# TimeTracker_TestboardV1.net
KiCad netlist of a schematic drawn in EAGLE
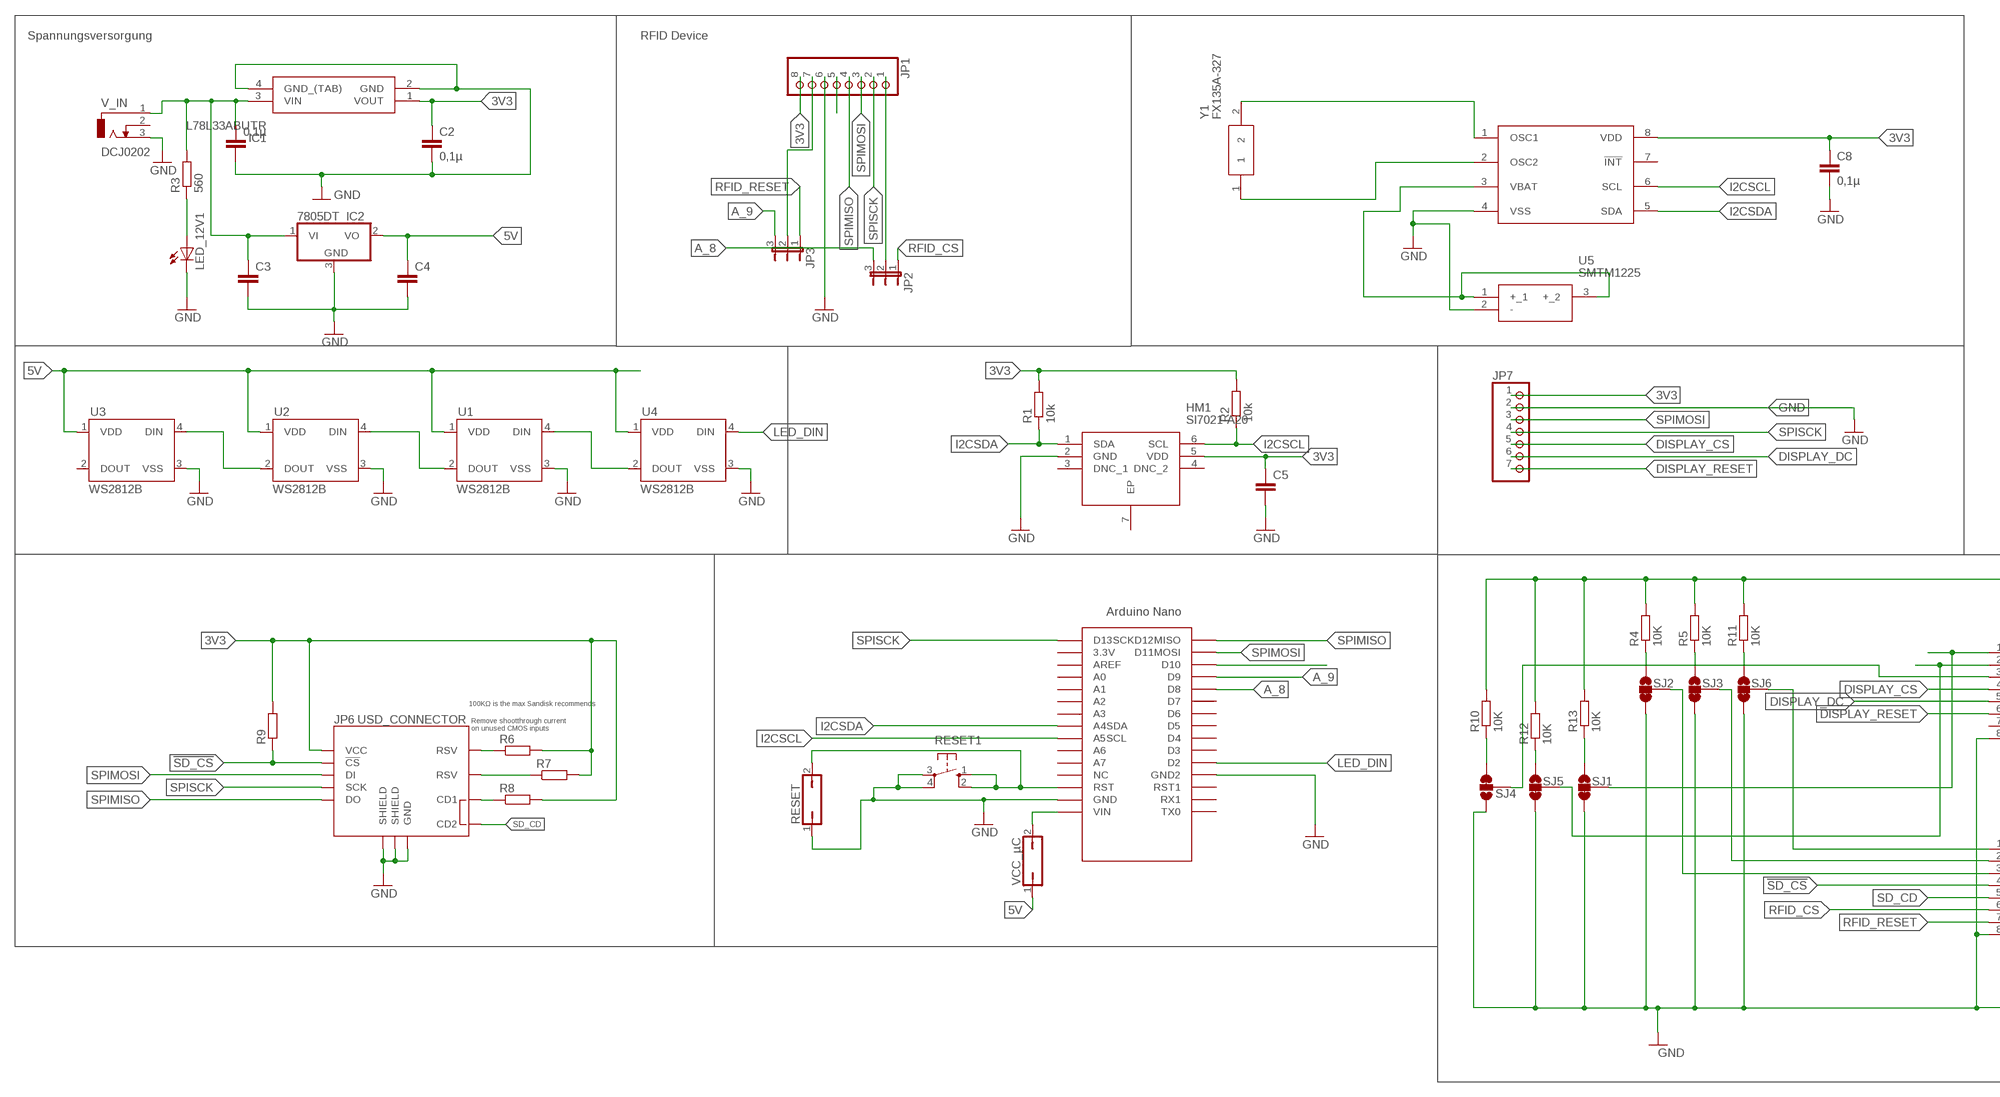
[diagram p0: schematic, sheet 1, part 1 of 2]
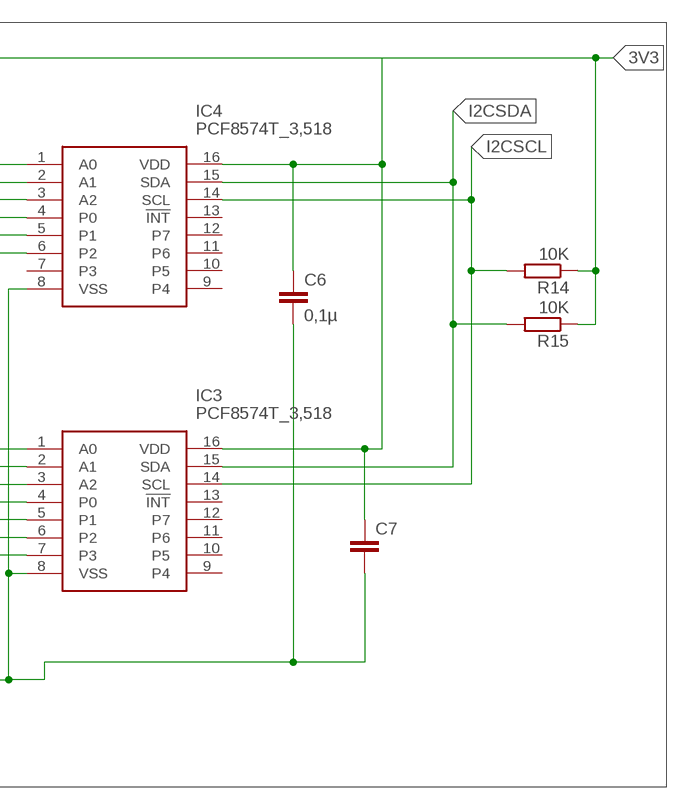
[diagram p1: schematic, sheet 1, part 2 of 2]

(export (version "E")
  (design (tool "Eeschema 10.0.6"))
  (components
    (comp (ref "0.1µ")
      (value "C-EUC0805")
      (footprint "eagle-import:C0805")
      (libsource (lib "eagle-import") (part "C-EUC0805"))
    )
    (comp (ref "C2")
      (value "0,1µ")
      (footprint "eagle-import:C0805")
      (libsource (lib "eagle-import") (part "C-EUC0805"))
    )
    (comp (ref "C3")
      (value "C-EUC0805")
      (footprint "eagle-import:C0805")
      (libsource (lib "eagle-import") (part "C-EUC0805"))
    )
    (comp (ref "C4")
      (value "C-EUC0805")
      (footprint "eagle-import:C0805")
      (libsource (lib "eagle-import") (part "C-EUC0805"))
    )
    (comp (ref "C5")
      (value "C-EUC0805")
      (footprint "eagle-import:C0805")
      (libsource (lib "eagle-import") (part "C-EUC0805"))
    )
    (comp (ref "C6")
      (value "0,1µ")
      (footprint "eagle-import:C0805")
      (libsource (lib "eagle-import") (part "C-EUC0805"))
    )
    (comp (ref "C7")
      (value "C-EUC0805")
      (footprint "eagle-import:C0805")
      (libsource (lib "eagle-import") (part "C-EUC0805"))
    )
    (comp (ref "C8")
      (value "0,1µ")
      (footprint "eagle-import:C0805")
      (libsource (lib "eagle-import") (part "C-EUC0805"))
    )
    (comp (ref "HM1")
      (value "SI7021-A20")
      (footprint "eagle-import:SON100P300X300X80-7N")
      (fields (field (name "MANUFACTURER_PART_NUMBER") "Si7021-A20"))
      (libsource (lib "eagle-import") (part "SI7021-A20"))
    )
    (comp (ref "IC1")
      (value "L78L33ABUTR")
      (footprint "eagle-import:ST-SOT-89")
      (fields
        (field (name "MOUSER_PART_NUMBER") "511-L78L33ABU-TR")
        (field (name "RS_PART_NUMBER") "6869464P")
      )
      (libsource (lib "eagle-import") (part "L78L33ABUTR"))
    )
    (comp (ref "IC2")
      (value "7805DT")
      (footprint "eagle-import:TO252")
      (libsource (lib "eagle-import") (part "78DT05"))
    )
    (comp (ref "IC3")
      (value "PCF8574T_3,518")
      (footprint "eagle-import:SOIC127P1032X265-16N")
      (fields
        (field (name "MANUFACTURER_PART_NUMBER") "PCF8574T/3,518")
        (field (name "MOUSER_PART_NUMBER") "771-PCF8574TD-T")
      )
      (libsource (lib "eagle-import") (part "PCF8574T_3,518"))
    )
    (comp (ref "IC4")
      (value "PCF8574T_3,518")
      (footprint "eagle-import:SOIC127P1032X265-16N")
      (fields
        (field (name "MANUFACTURER_PART_NUMBER") "PCF8574T/3,518")
        (field (name "MOUSER_PART_NUMBER") "771-PCF8574TD-T")
      )
      (libsource (lib "eagle-import") (part "PCF8574T_3,518"))
    )
    (comp (ref "JP1")
      (value "PINHD-1X8")
      (footprint "eagle-import:1X08")
      (libsource (lib "eagle-import") (part "PINHD-1X8"))
    )
    (comp (ref "JP2")
      (value "JP2E")
      (footprint "eagle-import:JP2")
      (libsource (lib "eagle-import") (part "JP2E"))
    )
    (comp (ref "JP3")
      (value "JP2E")
      (footprint "eagle-import:JP2")
      (libsource (lib "eagle-import") (part "JP2E"))
    )
    (comp (ref "JP6")
      (value "USD_CONNECTOR")
      (footprint "eagle-import:MICRO-SD-SOCKET-PP")
      (libsource (lib "eagle-import") (part "USD_CONNECTOR"))
    )
    (comp (ref "JP7")
      (value "PINHD-1X7")
      (footprint "eagle-import:1X07")
      (libsource (lib "eagle-import") (part "PINHD-1X7"))
    )
    (comp (ref "LED_12V1")
      (value "LEDSML0805")
      (footprint "eagle-import:SML0805")
      (libsource (lib "eagle-import") (part "LEDSML0805"))
    )
    (comp (ref "R1")
      (value "10k")
      (footprint "eagle-import:R0805")
      (libsource (lib "eagle-import") (part "R-EU_R0805"))
    )
    (comp (ref "R2")
      (value "10k")
      (footprint "eagle-import:R0805")
      (libsource (lib "eagle-import") (part "R-EU_R0805"))
    )
    (comp (ref "R3")
      (value "560")
      (footprint "eagle-import:R0805")
      (libsource (lib "eagle-import") (part "R-EU_R0805"))
    )
    (comp (ref "R4")
      (value "10K")
      (footprint "eagle-import:R0805")
      (libsource (lib "eagle-import") (part "R-EU_R0805"))
    )
    (comp (ref "R5")
      (value "10K")
      (footprint "eagle-import:R0805")
      (libsource (lib "eagle-import") (part "R-EU_R0805"))
    )
    (comp (ref "R6")
      (value "100k")
      (footprint "eagle-import:R0805")
      (libsource (lib "eagle-import") (part "R-EU_R0805"))
    )
    (comp (ref "R7")
      (value "100k")
      (footprint "eagle-import:R0805")
      (libsource (lib "eagle-import") (part "R-EU_R0805"))
    )
    (comp (ref "R8")
      (value "100k")
      (footprint "eagle-import:R0805")
      (libsource (lib "eagle-import") (part "R-EU_R0805"))
    )
    (comp (ref "R9")
      (value "100k")
      (footprint "eagle-import:R0805")
      (libsource (lib "eagle-import") (part "R-EU_R0805"))
    )
    (comp (ref "R10")
      (value "10K")
      (footprint "eagle-import:R0805")
      (libsource (lib "eagle-import") (part "R-EU_R0805"))
    )
    (comp (ref "R11")
      (value "10K")
      (footprint "eagle-import:R0805")
      (libsource (lib "eagle-import") (part "R-EU_R0805"))
    )
    (comp (ref "R12")
      (value "10K")
      (footprint "eagle-import:R0805")
      (libsource (lib "eagle-import") (part "R-EU_R0805"))
    )
    (comp (ref "R13")
      (value "10K")
      (footprint "eagle-import:R0805")
      (libsource (lib "eagle-import") (part "R-EU_R0805"))
    )
    (comp (ref "R14")
      (value "10K")
      (footprint "eagle-import:R0805")
      (libsource (lib "eagle-import") (part "R-EU_R0805"))
    )
    (comp (ref "R15")
      (value "10K")
      (footprint "eagle-import:R0805")
      (libsource (lib "eagle-import") (part "R-EU_R0805"))
    )
    (comp (ref "RESET")
      (value "JP1Q")
      (footprint "eagle-import:JP1")
      (libsource (lib "eagle-import") (part "JP1Q"))
    )
    (comp (ref "RESET1")
      (value "10-XX")
      (footprint "eagle-import:B3F-10XX")
      (fields (field (name "MPN") "B3F-1000"))
      (libsource (lib "eagle-import") (part "10-XX"))
    )
    (comp (ref "SJ1")
      (value "JUMPER-PAD-3-2OF3_NC_BY_TRACE_SMALL")
      (footprint "eagle-import:PAD-JUMPER-3-2OF3_NC_BY_TRACE_YES_SILK_FULL_BOX")
      (libsource (lib "eagle-import") (part "JUMPER-PAD-3-2OF3_NC_BY_TRACE_SMALL"))
    )
    (comp (ref "SJ2")
      (value "JUMPER-PAD-3-2OF3_NC_BY_TRACE_SMALL")
      (footprint "eagle-import:PAD-JUMPER-3-2OF3_NC_BY_TRACE_YES_SILK_FULL_BOX")
      (libsource (lib "eagle-import") (part "JUMPER-PAD-3-2OF3_NC_BY_TRACE_SMALL"))
    )
    (comp (ref "SJ3")
      (value "JUMPER-PAD-3-2OF3_NC_BY_TRACE_SMALL")
      (footprint "eagle-import:PAD-JUMPER-3-2OF3_NC_BY_TRACE_YES_SILK_FULL_BOX")
      (libsource (lib "eagle-import") (part "JUMPER-PAD-3-2OF3_NC_BY_TRACE_SMALL"))
    )
    (comp (ref "SJ4")
      (value "JUMPER-PAD-3-2OF3_NC_BY_TRACE_SMALL")
      (footprint "eagle-import:PAD-JUMPER-3-2OF3_NC_BY_TRACE_YES_SILK_FULL_BOX")
      (libsource (lib "eagle-import") (part "JUMPER-PAD-3-2OF3_NC_BY_TRACE_SMALL"))
    )
    (comp (ref "SJ5")
      (value "JUMPER-PAD-3-2OF3_NC_BY_TRACE_SMALL")
      (footprint "eagle-import:PAD-JUMPER-3-2OF3_NC_BY_TRACE_YES_SILK_FULL_BOX")
      (libsource (lib "eagle-import") (part "JUMPER-PAD-3-2OF3_NC_BY_TRACE_SMALL"))
    )
    (comp (ref "SJ6")
      (value "JUMPER-PAD-3-2OF3_NC_BY_TRACE_SMALL")
      (footprint "eagle-import:PAD-JUMPER-3-2OF3_NC_BY_TRACE_YES_SILK_FULL_BOX")
      (libsource (lib "eagle-import") (part "JUMPER-PAD-3-2OF3_NC_BY_TRACE_SMALL"))
    )
    (comp (ref "U$1")
      (value "NANO")
      (footprint "eagle-import:NANO")
      (libsource (lib "eagle-import") (part "NANO"))
    )
    (comp (ref "U$2")
      (value "RTC")
      (footprint "eagle-import:SOP65P490X110-8N")
      (libsource (lib "eagle-import") (part "RTC"))
    )
    (comp (ref "U1")
      (value "WS2812B")
      (footprint "eagle-import:WS2812B")
      (libsource (lib "eagle-import") (part "WS2812B"))
    )
    (comp (ref "U2")
      (value "WS2812B")
      (footprint "eagle-import:WS2812B")
      (libsource (lib "eagle-import") (part "WS2812B"))
    )
    (comp (ref "U3")
      (value "WS2812B")
      (footprint "eagle-import:WS2812B")
      (libsource (lib "eagle-import") (part "WS2812B"))
    )
    (comp (ref "U4")
      (value "WS2812B")
      (footprint "eagle-import:WS2812B")
      (libsource (lib "eagle-import") (part "WS2812B"))
    )
    (comp (ref "U5")
      (value "SMTM1225")
      (footprint "eagle-import:SMTM1225")
      (fields (field (name "MOUSER_PART_NUMBER") "614-SMTM1225"))
      (libsource (lib "eagle-import") (part "SMTM1225"))
    )
    (comp (ref "VCC_µC")
      (value "JP1Q")
      (footprint "eagle-import:JP1")
      (libsource (lib "eagle-import") (part "JP1Q"))
    )
    (comp (ref "V_IN")
      (value "DCJ0202")
      (footprint "eagle-import:DCJ0202")
      (libsource (lib "eagle-import") (part "DCJ0202"))
    )
    (comp (ref "Y1")
      (value "FX135A-327")
      (footprint "eagle-import:FX135")
      (fields (field (name "MOUSER_PART_NUMBER") "559-FX135A-327") (field (name "RS_PART_NUMBER") "6480200P"))
      (libsource (lib "eagle-import") (part "FX135A-327"))
    )
  )
  (nets
    (net (code "1") (name "/EP") (class "Default")
      (node (ref "HM1") (pin "7") (pinfunction "EP_7") (pintype "power_in"))
    )
    (net (code "2") (name "/~{SD_CS}") (class "Default")
      (node (ref "IC3") (pin "4") (pinfunction "P0_4") (pintype "bidirectional"))
      (node (ref "JP6") (pin "CS") (pinfunction "~{CS}_CS") (pintype "bidirectional"))
      (node (ref "R9") (pin "1") (pinfunction "1_1") (pintype "passive"))
    )
    (net (code "3") (name "3V3") (class "Default")
      (node (ref "C2") (pin "1") (pinfunction "1_1") (pintype "passive"))
      (node (ref "C5") (pin "1") (pinfunction "1_1") (pintype "passive"))
      (node (ref "C6") (pin "1") (pinfunction "1_1") (pintype "passive"))
      (node (ref "C7") (pin "1") (pinfunction "1_1") (pintype "passive"))
      (node (ref "C8") (pin "1") (pinfunction "1_1") (pintype "passive"))
      (node (ref "HM1") (pin "5") (pinfunction "VDD_5") (pintype "power_in"))
      (node (ref "IC1") (pin "1") (pinfunction "VOUT_1") (pintype "output"))
      (node (ref "IC3") (pin "16") (pinfunction "VDD_16") (pintype "bidirectional"))
      (node (ref "IC4") (pin "16") (pinfunction "VDD_16") (pintype "bidirectional"))
      (node (ref "JP1") (pin "8") (pinfunction "8_8") (pintype "passive"))
      (node (ref "JP6") (pin "VCC") (pinfunction "VCC_VCC") (pintype "bidirectional"))
      (node (ref "JP7") (pin "1") (pinfunction "1_1") (pintype "passive"))
      (node (ref "R1") (pin "2") (pinfunction "2_2") (pintype "passive"))
      (node (ref "R10") (pin "2") (pinfunction "2_2") (pintype "passive"))
      (node (ref "R11") (pin "2") (pinfunction "2_2") (pintype "passive"))
      (node (ref "R12") (pin "2") (pinfunction "2_2") (pintype "passive"))
      (node (ref "R13") (pin "2") (pinfunction "2_2") (pintype "passive"))
      (node (ref "R14") (pin "1") (pinfunction "1_1") (pintype "passive"))
      (node (ref "R15") (pin "1") (pinfunction "1_1") (pintype "passive"))
      (node (ref "R2") (pin "2") (pinfunction "2_2") (pintype "passive"))
      (node (ref "R4") (pin "2") (pinfunction "2_2") (pintype "passive"))
      (node (ref "R5") (pin "2") (pinfunction "2_2") (pintype "passive"))
      (node (ref "R6") (pin "2") (pinfunction "2_2") (pintype "passive"))
      (node (ref "R7") (pin "2") (pinfunction "2_2") (pintype "passive"))
      (node (ref "R8") (pin "2") (pinfunction "2_2") (pintype "passive"))
      (node (ref "R9") (pin "2") (pinfunction "2_2") (pintype "passive"))
      (node (ref "U$2") (pin "8") (pinfunction "VDD_8") (pintype "bidirectional"))
    )
    (net (code "4") (name "5V") (class "Default")
      (node (ref "C4") (pin "1") (pinfunction "1_1") (pintype "passive"))
      (node (ref "IC2") (pin "2") (pinfunction "VO_2") (pintype "passive"))
      (node (ref "U1") (pin "1") (pinfunction "VDD_1") (pintype "power_in"))
      (node (ref "U2") (pin "1") (pinfunction "VDD_1") (pintype "power_in"))
      (node (ref "U3") (pin "1") (pinfunction "VDD_1") (pintype "power_in"))
      (node (ref "U4") (pin "1") (pinfunction "VDD_1") (pintype "power_in"))
      (node (ref "VCC_µC") (pin "1") (pinfunction "1_1") (pintype "passive"))
    )
    (net (code "5") (name "A_8") (class "Default")
      (node (ref "JP2") (pin "3") (pinfunction "3_3") (pintype "passive"))
      (node (ref "U$1") (pin "D8") (pinfunction "D8_D8") (pintype "bidirectional"))
    )
    (net (code "6") (name "A_9") (class "Default")
      (node (ref "JP3") (pin "3") (pinfunction "3_3") (pintype "passive"))
      (node (ref "U$1") (pin "D9") (pinfunction "D9_D9") (pintype "bidirectional"))
    )
    (net (code "7") (name "DISPLAY_CS") (class "Default")
      (node (ref "IC4") (pin "4") (pinfunction "P0_4") (pintype "bidirectional"))
      (node (ref "JP7") (pin "5") (pinfunction "5_5") (pintype "passive"))
    )
    (net (code "8") (name "DISPLAY_DC") (class "Default")
      (node (ref "IC4") (pin "5") (pinfunction "P1_5") (pintype "bidirectional"))
      (node (ref "JP7") (pin "6") (pinfunction "6_6") (pintype "passive"))
    )
    (net (code "9") (name "DISPLAY_RESET") (class "Default")
      (node (ref "IC4") (pin "6") (pinfunction "P2_6") (pintype "bidirectional"))
      (node (ref "JP7") (pin "7") (pinfunction "7_7") (pintype "passive"))
    )
    (net (code "10") (name "GND") (class "Default")
      (node (ref "0.1µ") (pin "2") (pinfunction "2_2") (pintype "passive"))
      (node (ref "C2") (pin "2") (pinfunction "2_2") (pintype "passive"))
      (node (ref "C3") (pin "2") (pinfunction "2_2") (pintype "passive"))
      (node (ref "C4") (pin "2") (pinfunction "2_2") (pintype "passive"))
      (node (ref "C5") (pin "2") (pinfunction "2_2") (pintype "passive"))
      (node (ref "C6") (pin "2") (pinfunction "2_2") (pintype "passive"))
      (node (ref "C7") (pin "2") (pinfunction "2_2") (pintype "passive"))
      (node (ref "C8") (pin "2") (pinfunction "2_2") (pintype "passive"))
      (node (ref "HM1") (pin "2") (pinfunction "GND_2") (pintype "power_in"))
      (node (ref "IC1") (pin "2") (pinfunction "GND_2") (pintype "power_in"))
      (node (ref "IC1") (pin "4") (pinfunction "GND_(TAB)_4") (pintype "power_in"))
      (node (ref "IC2") (pin "3") (pinfunction "GND_3") (pintype "passive"))
      (node (ref "IC3") (pin "8") (pinfunction "VSS_8") (pintype "bidirectional"))
      (node (ref "IC4") (pin "8") (pinfunction "VSS_8") (pintype "bidirectional"))
      (node (ref "JP1") (pin "6") (pinfunction "6_6") (pintype "passive"))
      (node (ref "JP6") (pin "GND") (pinfunction "GND_GND") (pintype "bidirectional"))
      (node (ref "JP6") (pin "GND1") (pinfunction "SHIELD_GND1") (pintype "bidirectional"))
      (node (ref "JP6") (pin "GND3") (pinfunction "SHIELD_GND3") (pintype "bidirectional"))
      (node (ref "JP7") (pin "2") (pinfunction "2_2") (pintype "passive"))
      (node (ref "LED_12V1") (pin "C") (pinfunction "C_C") (pintype "passive"))
      (node (ref "RESET") (pin "1") (pinfunction "1_1") (pintype "passive"))
      (node (ref "RESET1") (pin "3") (pinfunction "P_3") (pintype "passive"))
      (node (ref "RESET1") (pin "4") (pinfunction "P1_4") (pintype "passive"))
      (node (ref "SJ1") (pin "3") (pinfunction "3_3") (pintype "passive"))
      (node (ref "SJ2") (pin "3") (pinfunction "3_3") (pintype "passive"))
      (node (ref "SJ3") (pin "3") (pinfunction "3_3") (pintype "passive"))
      (node (ref "SJ4") (pin "1") (pinfunction "1_1") (pintype "passive"))
      (node (ref "SJ5") (pin "3") (pinfunction "3_3") (pintype "passive"))
      (node (ref "SJ6") (pin "3") (pinfunction "3_3") (pintype "passive"))
      (node (ref "U$1") (pin "GND") (pinfunction "GND_GND") (pintype "bidirectional"))
      (node (ref "U$1") (pin "GND1") (pinfunction "GND2_GND1") (pintype "bidirectional"))
      (node (ref "U$2") (pin "4") (pinfunction "VSS_4") (pintype "bidirectional"))
      (node (ref "U1") (pin "3") (pinfunction "VSS_3") (pintype "power_in"))
      (node (ref "U2") (pin "3") (pinfunction "VSS_3") (pintype "power_in"))
      (node (ref "U3") (pin "3") (pinfunction "VSS_3") (pintype "power_in"))
      (node (ref "U4") (pin "3") (pinfunction "VSS_3") (pintype "power_in"))
      (node (ref "U5") (pin "2") (pinfunction "-_2") (pintype "bidirectional"))
      (node (ref "V_IN") (pin "3") (pinfunction "3_3") (pintype "passive"))
    )
    (net (code "11") (name "I2CSCL") (class "Default")
      (node (ref "HM1") (pin "6") (pinfunction "SCL_6") (pintype "bidirectional"))
      (node (ref "IC3") (pin "14") (pinfunction "SCL_14") (pintype "bidirectional"))
      (node (ref "IC4") (pin "14") (pinfunction "SCL_14") (pintype "bidirectional"))
      (node (ref "R14") (pin "2") (pinfunction "2_2") (pintype "passive"))
      (node (ref "R2") (pin "1") (pinfunction "1_1") (pintype "passive"))
      (node (ref "U$1") (pin "A5") (pinfunction "A5SCL_A5") (pintype "bidirectional"))
      (node (ref "U$2") (pin "6") (pinfunction "SCL_6") (pintype "bidirectional"))
    )
    (net (code "12") (name "I2CSDA") (class "Default")
      (node (ref "HM1") (pin "1") (pinfunction "SDA_1") (pintype "bidirectional"))
      (node (ref "IC3") (pin "15") (pinfunction "SDA_15") (pintype "bidirectional"))
      (node (ref "IC4") (pin "15") (pinfunction "SDA_15") (pintype "bidirectional"))
      (node (ref "R1") (pin "1") (pinfunction "1_1") (pintype "passive"))
      (node (ref "R15") (pin "2") (pinfunction "2_2") (pintype "passive"))
      (node (ref "U$1") (pin "A4") (pinfunction "A4SDA_A4") (pintype "bidirectional"))
      (node (ref "U$2") (pin "5") (pinfunction "SDA_5") (pintype "bidirectional"))
    )
    (net (code "13") (name "LED_DIN") (class "Default")
      (node (ref "U$1") (pin "D2") (pinfunction "D2_D2") (pintype "bidirectional"))
      (node (ref "U4") (pin "4") (pinfunction "DIN_4") (pintype "input"))
    )
    (net (code "14") (name "Net-(IC1-VIN)") (class "Default")
      (node (ref "0.1µ") (pin "1") (pinfunction "1_1") (pintype "passive"))
      (node (ref "C3") (pin "1") (pinfunction "1_1") (pintype "passive"))
      (node (ref "IC1") (pin "3") (pinfunction "VIN_3") (pintype "input"))
      (node (ref "IC2") (pin "1") (pinfunction "VI_1") (pintype "input"))
      (node (ref "R3") (pin "2") (pinfunction "2_2") (pintype "passive"))
      (node (ref "V_IN") (pin "1") (pinfunction "1_1") (pintype "passive"))
    )
    (net (code "15") (name "Net-(IC3-A0)") (class "Default")
      (node (ref "IC3") (pin "1") (pinfunction "A0_1") (pintype "bidirectional"))
      (node (ref "SJ6") (pin "2") (pinfunction "2_2") (pintype "passive"))
    )
    (net (code "16") (name "Net-(IC3-A1)") (class "Default")
      (node (ref "IC3") (pin "2") (pinfunction "A1_2") (pintype "bidirectional"))
      (node (ref "SJ3") (pin "2") (pinfunction "2_2") (pintype "passive"))
    )
    (net (code "17") (name "Net-(IC3-A2)") (class "Default")
      (node (ref "IC3") (pin "3") (pinfunction "A2_3") (pintype "bidirectional"))
      (node (ref "SJ2") (pin "2") (pinfunction "2_2") (pintype "passive"))
    )
    (net (code "18") (name "Net-(IC4-A0)") (class "Default")
      (node (ref "IC4") (pin "1") (pinfunction "A0_1") (pintype "bidirectional"))
      (node (ref "SJ1") (pin "2") (pinfunction "2_2") (pintype "passive"))
    )
    (net (code "19") (name "Net-(IC4-A1)") (class "Default")
      (node (ref "IC4") (pin "2") (pinfunction "A1_2") (pintype "bidirectional"))
      (node (ref "SJ5") (pin "2") (pinfunction "2_2") (pintype "passive"))
    )
    (net (code "20") (name "Net-(IC4-A2)") (class "Default")
      (node (ref "IC4") (pin "3") (pinfunction "A2_3") (pintype "bidirectional"))
      (node (ref "SJ4") (pin "2") (pinfunction "2_2") (pintype "passive"))
    )
    (net (code "21") (name "Net-(JP1-Pad1)") (class "Default")
      (node (ref "JP1") (pin "1") (pinfunction "1_1") (pintype "passive"))
      (node (ref "JP2") (pin "2") (pinfunction "2_2") (pintype "passive"))
    )
    (net (code "22") (name "Net-(JP1-Pad7)") (class "Default")
      (node (ref "JP1") (pin "7") (pinfunction "7_7") (pintype "passive"))
      (node (ref "JP3") (pin "2") (pinfunction "2_2") (pintype "passive"))
    )
    (net (code "23") (name "Net-(JP6-PadCD1)") (class "Default")
      (node (ref "JP6") (pin "CD1") (pinfunction "CD1_CD1") (pintype "bidirectional"))
      (node (ref "R8") (pin "1") (pinfunction "1_1") (pintype "passive"))
    )
    (net (code "24") (name "Net-(JP6-RSV-PadRSV1)") (class "Default")
      (node (ref "JP6") (pin "RSV1") (pinfunction "RSV_RSV1") (pintype "bidirectional"))
      (node (ref "R6") (pin "1") (pinfunction "1_1") (pintype "passive"))
    )
    (net (code "25") (name "Net-(JP6-RSV-PadRSV2)") (class "Default")
      (node (ref "JP6") (pin "RSV2") (pinfunction "RSV_RSV2") (pintype "bidirectional"))
      (node (ref "R7") (pin "1") (pinfunction "1_1") (pintype "passive"))
    )
    (net (code "26") (name "Net-(LED_12V1-PadA)") (class "Default")
      (node (ref "LED_12V1") (pin "A") (pinfunction "A_A") (pintype "passive"))
      (node (ref "R3") (pin "1") (pinfunction "1_1") (pintype "passive"))
    )
    (net (code "27") (name "Net-(R4-Pad1)") (class "Default")
      (node (ref "R4") (pin "1") (pinfunction "1_1") (pintype "passive"))
      (node (ref "SJ2") (pin "1") (pinfunction "1_1") (pintype "passive"))
    )
    (net (code "28") (name "Net-(R5-Pad1)") (class "Default")
      (node (ref "R5") (pin "1") (pinfunction "1_1") (pintype "passive"))
      (node (ref "SJ3") (pin "1") (pinfunction "1_1") (pintype "passive"))
    )
    (net (code "29") (name "Net-(R10-Pad1)") (class "Default")
      (node (ref "R10") (pin "1") (pinfunction "1_1") (pintype "passive"))
      (node (ref "SJ4") (pin "3") (pinfunction "3_3") (pintype "passive"))
    )
    (net (code "30") (name "Net-(R11-Pad1)") (class "Default")
      (node (ref "R11") (pin "1") (pinfunction "1_1") (pintype "passive"))
      (node (ref "SJ6") (pin "1") (pinfunction "1_1") (pintype "passive"))
    )
    (net (code "31") (name "Net-(R12-Pad1)") (class "Default")
      (node (ref "R12") (pin "1") (pinfunction "1_1") (pintype "passive"))
      (node (ref "SJ5") (pin "1") (pinfunction "1_1") (pintype "passive"))
    )
    (net (code "32") (name "Net-(R13-Pad1)") (class "Default")
      (node (ref "R13") (pin "1") (pinfunction "1_1") (pintype "passive"))
      (node (ref "SJ1") (pin "1") (pinfunction "1_1") (pintype "passive"))
    )
    (net (code "33") (name "Net-(RESET1-S)") (class "Default")
      (node (ref "RESET") (pin "2") (pinfunction "2_2") (pintype "passive"))
      (node (ref "RESET1") (pin "1") (pinfunction "S_1") (pintype "passive"))
      (node (ref "RESET1") (pin "2") (pinfunction "S1_2") (pintype "passive"))
      (node (ref "U$1") (pin "RST") (pinfunction "RST_RST") (pintype "bidirectional"))
    )
    (net (code "34") (name "Net-(U$1-VIN)") (class "Default")
      (node (ref "U$1") (pin "RAW") (pinfunction "VIN_RAW") (pintype "bidirectional"))
      (node (ref "VCC_µC") (pin "2") (pinfunction "2_2") (pintype "passive"))
    )
    (net (code "35") (name "Net-(U$2-OSC1)") (class "Default")
      (node (ref "U$2") (pin "1") (pinfunction "OSC1_1") (pintype "bidirectional"))
      (node (ref "Y1") (pin "2") (pinfunction "2_2") (pintype "bidirectional"))
    )
    (net (code "36") (name "Net-(U$2-OSC2)") (class "Default")
      (node (ref "U$2") (pin "2") (pinfunction "OSC2_2") (pintype "bidirectional"))
      (node (ref "Y1") (pin "1") (pinfunction "1_1") (pintype "bidirectional"))
    )
    (net (code "37") (name "Net-(U$2-VBAT)") (class "Default")
      (node (ref "U$2") (pin "3") (pinfunction "VBAT_3") (pintype "bidirectional"))
      (node (ref "U5") (pin "1") (pinfunction "+_1_1") (pintype "bidirectional"))
      (node (ref "U5") (pin "3") (pinfunction "+_2_3") (pintype "bidirectional"))
    )
    (net (code "38") (name "Net-(U1-DIN)") (class "Default")
      (node (ref "U1") (pin "4") (pinfunction "DIN_4") (pintype "input"))
      (node (ref "U4") (pin "2") (pinfunction "DOUT_2") (pintype "output"))
    )
    (net (code "39") (name "Net-(U1-DOUT)") (class "Default")
      (node (ref "U1") (pin "2") (pinfunction "DOUT_2") (pintype "output"))
      (node (ref "U2") (pin "4") (pinfunction "DIN_4") (pintype "input"))
    )
    (net (code "40") (name "Net-(U2-DOUT)") (class "Default")
      (node (ref "U2") (pin "2") (pinfunction "DOUT_2") (pintype "output"))
      (node (ref "U3") (pin "4") (pinfunction "DIN_4") (pintype "input"))
    )
    (net (code "41") (name "RFID_CS") (class "Default")
      (node (ref "IC3") (pin "6") (pinfunction "P2_6") (pintype "bidirectional"))
      (node (ref "JP2") (pin "1") (pinfunction "1_1") (pintype "passive"))
    )
    (net (code "42") (name "RFID_RESET") (class "Default")
      (node (ref "IC3") (pin "7") (pinfunction "P3_7") (pintype "bidirectional"))
      (node (ref "JP3") (pin "1") (pinfunction "1_1") (pintype "passive"))
    )
    (net (code "43") (name "SD_CD") (class "Default")
      (node (ref "IC3") (pin "5") (pinfunction "P1_5") (pintype "bidirectional"))
      (node (ref "JP6") (pin "CD2") (pinfunction "CD2_CD2") (pintype "bidirectional"))
    )
    (net (code "44") (name "SPIMISO") (class "Default")
      (node (ref "JP1") (pin "4") (pinfunction "4_4") (pintype "passive"))
      (node (ref "JP6") (pin "DO") (pinfunction "DO_DO") (pintype "bidirectional"))
      (node (ref "U$1") (pin "D12") (pinfunction "D12MISO_D12") (pintype "bidirectional"))
    )
    (net (code "45") (name "SPIMOSI") (class "Default")
      (node (ref "JP1") (pin "3") (pinfunction "3_3") (pintype "passive"))
      (node (ref "JP6") (pin "DI") (pinfunction "DI_DI") (pintype "bidirectional"))
      (node (ref "JP7") (pin "3") (pinfunction "3_3") (pintype "passive"))
      (node (ref "U$1") (pin "D11") (pinfunction "D11MOSI_D11") (pintype "bidirectional"))
    )
    (net (code "46") (name "SPISCK") (class "Default")
      (node (ref "JP1") (pin "2") (pinfunction "2_2") (pintype "passive"))
      (node (ref "JP6") (pin "SCLK") (pinfunction "SCK_SCLK") (pintype "bidirectional"))
      (node (ref "JP7") (pin "4") (pinfunction "4_4") (pintype "passive"))
      (node (ref "U$1") (pin "D13") (pinfunction "D13SCK_D13") (pintype "bidirectional"))
    )
    (net (code "47") (name "unconnected-(HM1-DNC_1-Pad3)") (class "Default")
      (node (ref "HM1") (pin "3") (pinfunction "DNC_1_3") (pintype "bidirectional"))
    )
    (net (code "48") (name "unconnected-(HM1-DNC_2-Pad4)") (class "Default")
      (node (ref "HM1") (pin "4") (pinfunction "DNC_2_4") (pintype "bidirectional"))
    )
    (net (code "49") (name "unconnected-(IC3-P4-Pad9)") (class "Default")
      (node (ref "IC3") (pin "9") (pinfunction "P4_9") (pintype "bidirectional"))
    )
    (net (code "50") (name "unconnected-(IC3-P5-Pad10)") (class "Default")
      (node (ref "IC3") (pin "10") (pinfunction "P5_10") (pintype "bidirectional"))
    )
    (net (code "51") (name "unconnected-(IC3-P6-Pad11)") (class "Default")
      (node (ref "IC3") (pin "11") (pinfunction "P6_11") (pintype "bidirectional"))
    )
    (net (code "52") (name "unconnected-(IC3-P7-Pad12)") (class "Default")
      (node (ref "IC3") (pin "12") (pinfunction "P7_12") (pintype "bidirectional"))
    )
    (net (code "53") (name "unconnected-(IC3-~{INT}-Pad13)") (class "Default")
      (node (ref "IC3") (pin "13") (pinfunction "~{INT}_13") (pintype "bidirectional"))
    )
    (net (code "54") (name "unconnected-(IC4-P3-Pad7)") (class "Default")
      (node (ref "IC4") (pin "7") (pinfunction "P3_7") (pintype "bidirectional"))
    )
    (net (code "55") (name "unconnected-(IC4-P4-Pad9)") (class "Default")
      (node (ref "IC4") (pin "9") (pinfunction "P4_9") (pintype "bidirectional"))
    )
    (net (code "56") (name "unconnected-(IC4-P5-Pad10)") (class "Default")
      (node (ref "IC4") (pin "10") (pinfunction "P5_10") (pintype "bidirectional"))
    )
    (net (code "57") (name "unconnected-(IC4-P6-Pad11)") (class "Default")
      (node (ref "IC4") (pin "11") (pinfunction "P6_11") (pintype "bidirectional"))
    )
    (net (code "58") (name "unconnected-(IC4-P7-Pad12)") (class "Default")
      (node (ref "IC4") (pin "12") (pinfunction "P7_12") (pintype "bidirectional"))
    )
    (net (code "59") (name "unconnected-(IC4-~{INT}-Pad13)") (class "Default")
      (node (ref "IC4") (pin "13") (pinfunction "~{INT}_13") (pintype "bidirectional"))
    )
    (net (code "60") (name "unconnected-(JP1-Pad5)") (class "Default")
      (node (ref "JP1") (pin "5") (pinfunction "5_5") (pintype "passive"))
    )
    (net (code "61") (name "unconnected-(U$1-NC-Pad5V)") (class "Default")
      (node (ref "U$1") (pin "5V") (pinfunction "NC_5V") (pintype "bidirectional"))
    )
    (net (code "62") (name "unconnected-(U$1-Pad3.3V)") (class "Default")
      (node (ref "U$1") (pin "3.3V") (pinfunction "3.3V_3.3V") (pintype "bidirectional"))
    )
    (net (code "63") (name "unconnected-(U$1-PadA0)") (class "Default")
      (node (ref "U$1") (pin "A0") (pinfunction "A0_A0") (pintype "bidirectional"))
    )
    (net (code "64") (name "unconnected-(U$1-PadA1)") (class "Default")
      (node (ref "U$1") (pin "A1") (pinfunction "A1_A1") (pintype "bidirectional"))
    )
    (net (code "65") (name "unconnected-(U$1-PadA2)") (class "Default")
      (node (ref "U$1") (pin "A2") (pinfunction "A2_A2") (pintype "bidirectional"))
    )
    (net (code "66") (name "unconnected-(U$1-PadA3)") (class "Default")
      (node (ref "U$1") (pin "A3") (pinfunction "A3_A3") (pintype "bidirectional"))
    )
    (net (code "67") (name "unconnected-(U$1-PadA6)") (class "Default")
      (node (ref "U$1") (pin "A6") (pinfunction "A6_A6") (pintype "bidirectional"))
    )
    (net (code "68") (name "unconnected-(U$1-PadA7)") (class "Default")
      (node (ref "U$1") (pin "A7") (pinfunction "A7_A7") (pintype "bidirectional"))
    )
    (net (code "69") (name "unconnected-(U$1-PadAREF)") (class "Default")
      (node (ref "U$1") (pin "AREF") (pinfunction "AREF_AREF") (pintype "bidirectional"))
    )
    (net (code "70") (name "unconnected-(U$1-PadD3)") (class "Default")
      (node (ref "U$1") (pin "D3") (pinfunction "D3_D3") (pintype "bidirectional"))
    )
    (net (code "71") (name "unconnected-(U$1-PadD4)") (class "Default")
      (node (ref "U$1") (pin "D4") (pinfunction "D4_D4") (pintype "bidirectional"))
    )
    (net (code "72") (name "unconnected-(U$1-PadD5)") (class "Default")
      (node (ref "U$1") (pin "D5") (pinfunction "D5_D5") (pintype "bidirectional"))
    )
    (net (code "73") (name "unconnected-(U$1-PadD6)") (class "Default")
      (node (ref "U$1") (pin "D6") (pinfunction "D6_D6") (pintype "bidirectional"))
    )
    (net (code "74") (name "unconnected-(U$1-PadD7)") (class "Default")
      (node (ref "U$1") (pin "D7") (pinfunction "D7_D7") (pintype "bidirectional"))
    )
    (net (code "75") (name "unconnected-(U$1-PadD10)") (class "Default")
      (node (ref "U$1") (pin "D10") (pinfunction "D10_D10") (pintype "bidirectional"))
    )
    (net (code "76") (name "unconnected-(U$1-PadRST1)") (class "Default")
      (node (ref "U$1") (pin "RST1") (pinfunction "RST1_RST1") (pintype "bidirectional"))
    )
    (net (code "77") (name "unconnected-(U$1-PadRX1)") (class "Default")
      (node (ref "U$1") (pin "RX1") (pinfunction "RX1_RX1") (pintype "bidirectional"))
    )
    (net (code "78") (name "unconnected-(U$1-PadTX0)") (class "Default")
      (node (ref "U$1") (pin "TX0") (pinfunction "TX0_TX0") (pintype "bidirectional"))
    )
    (net (code "79") (name "unconnected-(U$2-~{INT}-Pad7)") (class "Default")
      (node (ref "U$2") (pin "7") (pinfunction "~{INT}_7") (pintype "bidirectional"))
    )
    (net (code "80") (name "unconnected-(U3-DOUT-Pad2)") (class "Default")
      (node (ref "U3") (pin "2") (pinfunction "DOUT_2") (pintype "output"))
    )
    (net (code "81") (name "unconnected-(V_IN-Pad2)") (class "Default")
      (node (ref "V_IN") (pin "2") (pinfunction "2_2") (pintype "passive"))
    )
  )
)
